# main.net
KiCad netlist of a schematic drawn in EAGLE
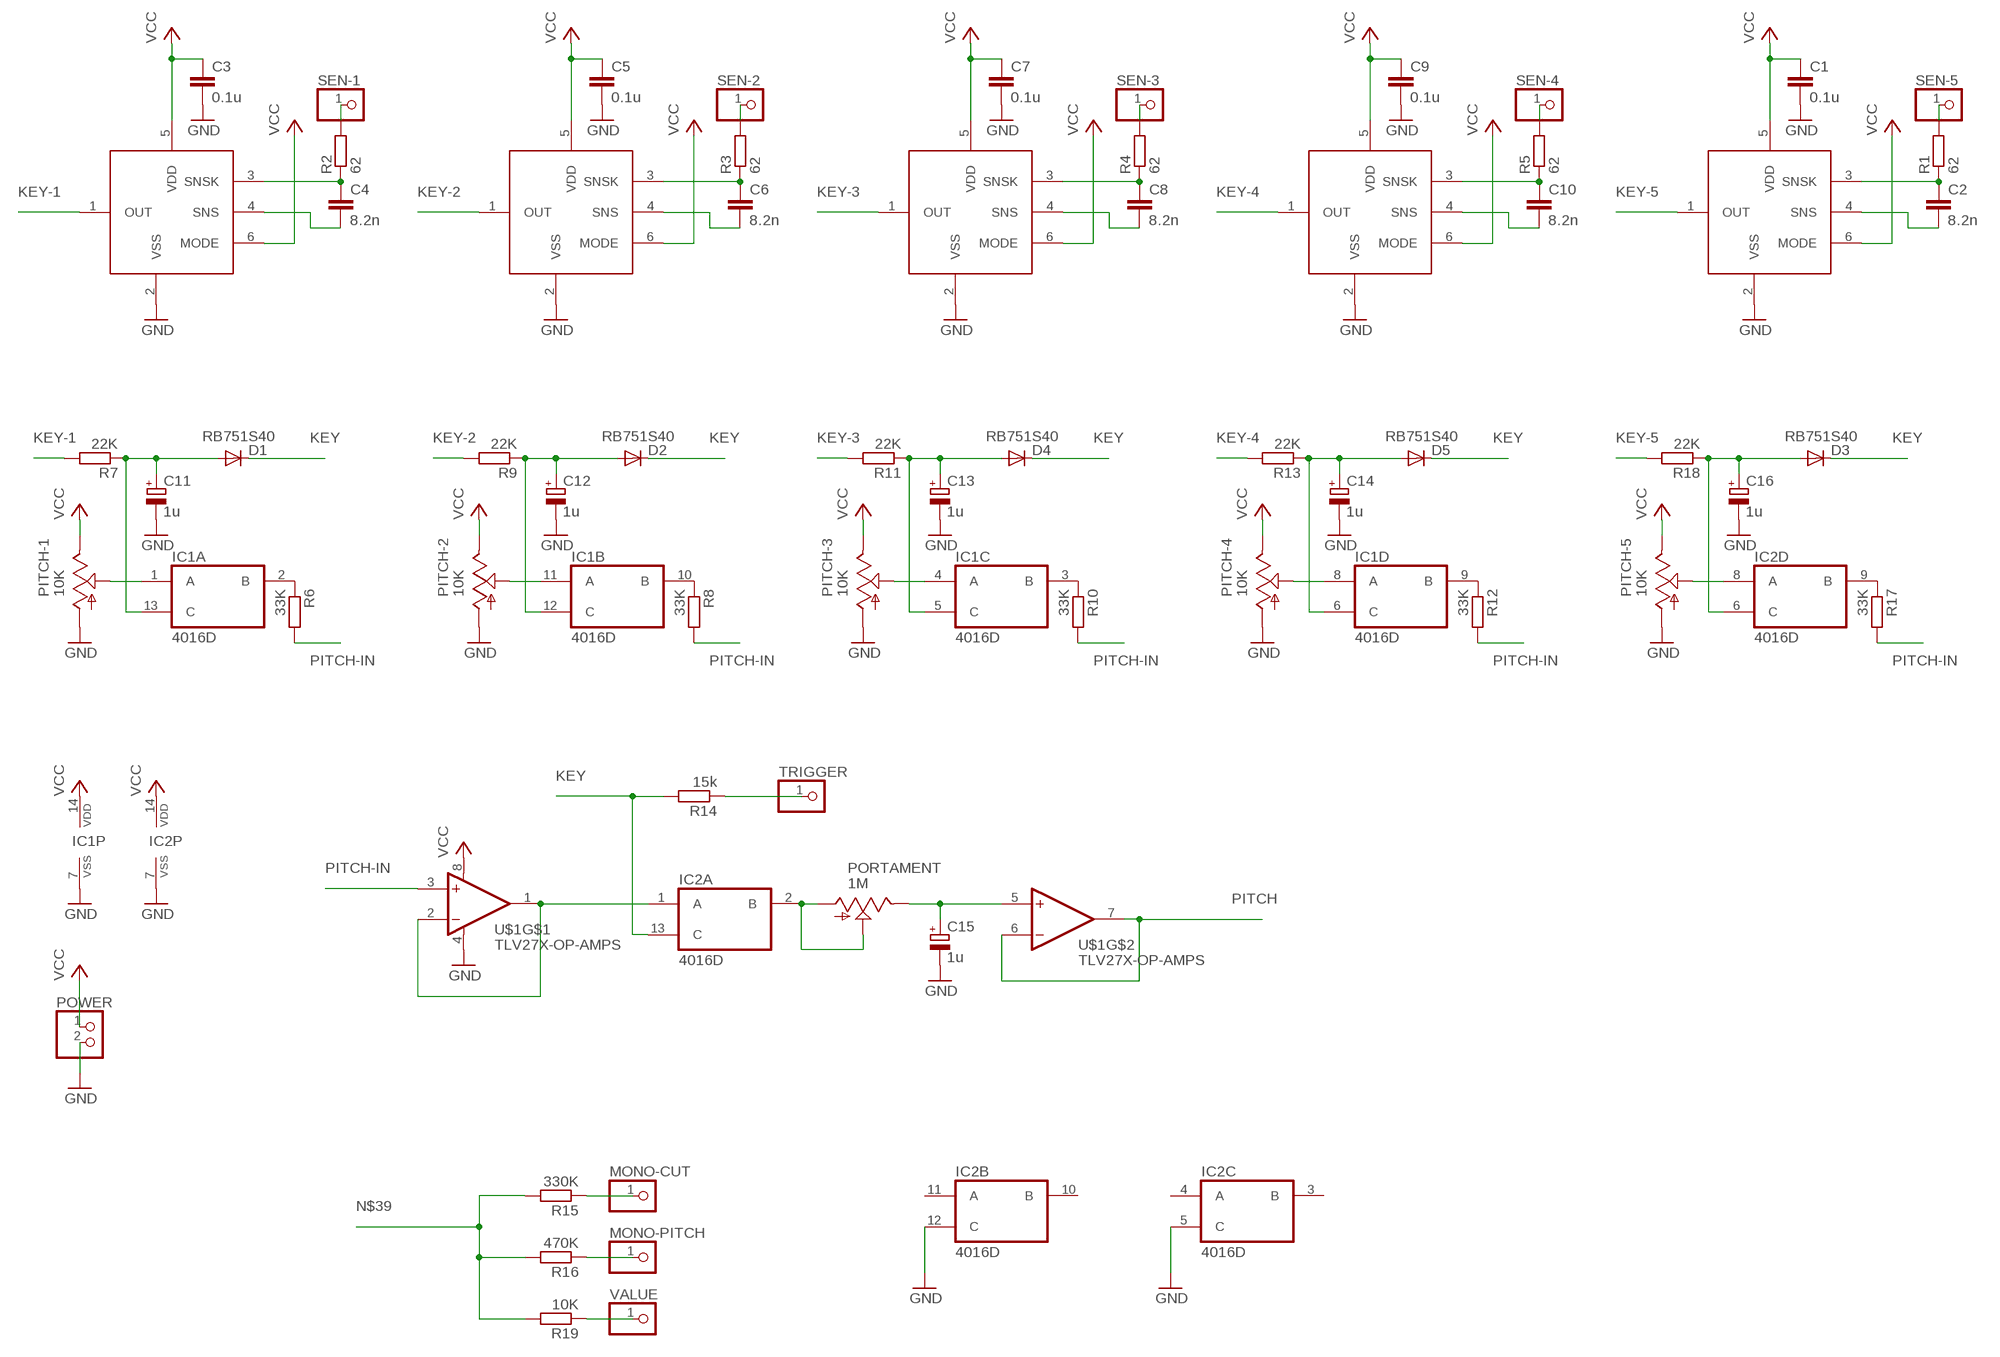
[diagram p0: schematic, sheet 1]

(export (version "E")
  (design (tool "Eeschema 10.0.6"))
  (components
    (comp (ref "C1")
      (value "0.1u")
      (footprint "eagle-import:C0805")
      (libsource (lib "eagle-import") (part "C-EUC0805"))
    )
    (comp (ref "C2")
      (value "8.2n")
      (footprint "eagle-import:C0805")
      (libsource (lib "eagle-import") (part "C-EUC0805"))
    )
    (comp (ref "C3")
      (value "0.1u")
      (footprint "eagle-import:C0805")
      (libsource (lib "eagle-import") (part "C-EUC0805"))
    )
    (comp (ref "C4")
      (value "8.2n")
      (footprint "eagle-import:C0805")
      (libsource (lib "eagle-import") (part "C-EUC0805"))
    )
    (comp (ref "C5")
      (value "0.1u")
      (footprint "eagle-import:C0805")
      (libsource (lib "eagle-import") (part "C-EUC0805"))
    )
    (comp (ref "C6")
      (value "8.2n")
      (footprint "eagle-import:C0805")
      (libsource (lib "eagle-import") (part "C-EUC0805"))
    )
    (comp (ref "C7")
      (value "0.1u")
      (footprint "eagle-import:C0805")
      (libsource (lib "eagle-import") (part "C-EUC0805"))
    )
    (comp (ref "C8")
      (value "8.2n")
      (footprint "eagle-import:C0805")
      (libsource (lib "eagle-import") (part "C-EUC0805"))
    )
    (comp (ref "C9")
      (value "0.1u")
      (footprint "eagle-import:C0805")
      (libsource (lib "eagle-import") (part "C-EUC0805"))
    )
    (comp (ref "C10")
      (value "8.2n")
      (footprint "eagle-import:C0805")
      (libsource (lib "eagle-import") (part "C-EUC0805"))
    )
    (comp (ref "C11")
      (value "1u")
      (footprint "eagle-import:PANASONIC_A")
      (libsource (lib "eagle-import") (part "CPOL-EUA"))
    )
    (comp (ref "C12")
      (value "1u")
      (footprint "eagle-import:PANASONIC_A")
      (libsource (lib "eagle-import") (part "CPOL-EUA"))
    )
    (comp (ref "C13")
      (value "1u")
      (footprint "eagle-import:PANASONIC_A")
      (libsource (lib "eagle-import") (part "CPOL-EUA"))
    )
    (comp (ref "C14")
      (value "1u")
      (footprint "eagle-import:PANASONIC_A")
      (libsource (lib "eagle-import") (part "CPOL-EUA"))
    )
    (comp (ref "C15")
      (value "1u")
      (footprint "eagle-import:PANASONIC_A")
      (libsource (lib "eagle-import") (part "CPOL-EUA"))
    )
    (comp (ref "C16")
      (value "1u")
      (footprint "eagle-import:PANASONIC_A")
      (libsource (lib "eagle-import") (part "CPOL-EUA"))
    )
    (comp (ref "D1")
      (value "RB751S40")
      (footprint "eagle-import:SOD523")
      (libsource (lib "eagle-import") (part "DIODE-SOD523"))
    )
    (comp (ref "D2")
      (value "RB751S40")
      (footprint "eagle-import:SOD523")
      (libsource (lib "eagle-import") (part "DIODE-SOD523"))
    )
    (comp (ref "D3")
      (value "RB751S40")
      (footprint "eagle-import:SOD523")
      (libsource (lib "eagle-import") (part "DIODE-SOD523"))
    )
    (comp (ref "D4")
      (value "RB751S40")
      (footprint "eagle-import:SOD523")
      (libsource (lib "eagle-import") (part "DIODE-SOD523"))
    )
    (comp (ref "D5")
      (value "RB751S40")
      (footprint "eagle-import:SOD523")
      (libsource (lib "eagle-import") (part "DIODE-SOD523"))
    )
    (comp (ref "IC1")
      (value "4016D")
      (footprint "eagle-import:SO14")
      (libsource (lib "eagle-import") (part "4016D"))
    )
    (comp (ref "IC2")
      (value "4016D")
      (footprint "eagle-import:SO14")
      (libsource (lib "eagle-import") (part "4016D"))
    )
    (comp (ref "MONO-CUT")
      (value "PINHD-1X1")
      (footprint "eagle-import:1X01")
      (libsource (lib "eagle-import") (part "PINHD-1X1"))
    )
    (comp (ref "MONO-PITCH")
      (value "PINHD-1X1")
      (footprint "eagle-import:1X01")
      (libsource (lib "eagle-import") (part "PINHD-1X1"))
    )
    (comp (ref "PITCH-1")
      (value "10K")
      (footprint "eagle-import:PIN-1X03")
      (libsource (lib "eagle-import") (part "POT-PINHEADSTRAIGHT"))
    )
    (comp (ref "PITCH-2")
      (value "10K")
      (footprint "eagle-import:PIN-1X03")
      (libsource (lib "eagle-import") (part "POT-PINHEADSTRAIGHT"))
    )
    (comp (ref "PITCH-3")
      (value "10K")
      (footprint "eagle-import:PIN-1X03")
      (libsource (lib "eagle-import") (part "POT-PINHEADSTRAIGHT"))
    )
    (comp (ref "PITCH-4")
      (value "10K")
      (footprint "eagle-import:PIN-1X03")
      (libsource (lib "eagle-import") (part "POT-PINHEADSTRAIGHT"))
    )
    (comp (ref "PITCH-5")
      (value "10K")
      (footprint "eagle-import:PIN-1X03")
      (libsource (lib "eagle-import") (part "POT-PINHEADSTRAIGHT"))
    )
    (comp (ref "PORTAMENT")
      (value "1M")
      (footprint "eagle-import:PIN-1X03")
      (libsource (lib "eagle-import") (part "POT-PINHEADSTRAIGHT"))
    )
    (comp (ref "POWER")
      (value "PINHD-1X2")
      (footprint "eagle-import:1X02")
      (libsource (lib "eagle-import") (part "PINHD-1X2"))
    )
    (comp (ref "R1")
      (value "62")
      (footprint "eagle-import:R0805")
      (libsource (lib "eagle-import") (part "R-EU_R0805"))
    )
    (comp (ref "R2")
      (value "62")
      (footprint "eagle-import:R0805")
      (libsource (lib "eagle-import") (part "R-EU_R0805"))
    )
    (comp (ref "R3")
      (value "62")
      (footprint "eagle-import:R0805")
      (libsource (lib "eagle-import") (part "R-EU_R0805"))
    )
    (comp (ref "R4")
      (value "62")
      (footprint "eagle-import:R0805")
      (libsource (lib "eagle-import") (part "R-EU_R0805"))
    )
    (comp (ref "R5")
      (value "62")
      (footprint "eagle-import:R0805")
      (libsource (lib "eagle-import") (part "R-EU_R0805"))
    )
    (comp (ref "R6")
      (value "33K")
      (footprint "eagle-import:R0805")
      (libsource (lib "eagle-import") (part "R-EU_R0805"))
    )
    (comp (ref "R7")
      (value "22K")
      (footprint "eagle-import:R0805")
      (libsource (lib "eagle-import") (part "R-EU_R0805"))
    )
    (comp (ref "R8")
      (value "33K")
      (footprint "eagle-import:R0805")
      (libsource (lib "eagle-import") (part "R-EU_R0805"))
    )
    (comp (ref "R9")
      (value "22K")
      (footprint "eagle-import:R0805")
      (libsource (lib "eagle-import") (part "R-EU_R0805"))
    )
    (comp (ref "R10")
      (value "33K")
      (footprint "eagle-import:R0805")
      (libsource (lib "eagle-import") (part "R-EU_R0805"))
    )
    (comp (ref "R11")
      (value "22K")
      (footprint "eagle-import:R0805")
      (libsource (lib "eagle-import") (part "R-EU_R0805"))
    )
    (comp (ref "R12")
      (value "33K")
      (footprint "eagle-import:R0805")
      (libsource (lib "eagle-import") (part "R-EU_R0805"))
    )
    (comp (ref "R13")
      (value "22K")
      (footprint "eagle-import:R0805")
      (libsource (lib "eagle-import") (part "R-EU_R0805"))
    )
    (comp (ref "R14")
      (value "15k")
      (footprint "eagle-import:R0805")
      (libsource (lib "eagle-import") (part "R-EU_R0805"))
    )
    (comp (ref "R15")
      (value "330K")
      (footprint "eagle-import:R0805")
      (libsource (lib "eagle-import") (part "R-EU_R0805"))
    )
    (comp (ref "R16")
      (value "470K")
      (footprint "eagle-import:R0805")
      (libsource (lib "eagle-import") (part "R-EU_R0805"))
    )
    (comp (ref "R17")
      (value "33K")
      (footprint "eagle-import:R0805")
      (libsource (lib "eagle-import") (part "R-EU_R0805"))
    )
    (comp (ref "R18")
      (value "22K")
      (footprint "eagle-import:R0805")
      (libsource (lib "eagle-import") (part "R-EU_R0805"))
    )
    (comp (ref "R19")
      (value "10K")
      (footprint "eagle-import:R0805")
      (libsource (lib "eagle-import") (part "R-EU_R0805"))
    )
    (comp (ref "SEN-1")
      (value "PINHD-1X1")
      (footprint "eagle-import:1X01")
      (libsource (lib "eagle-import") (part "PINHD-1X1"))
    )
    (comp (ref "SEN-2")
      (value "PINHD-1X1")
      (footprint "eagle-import:1X01")
      (libsource (lib "eagle-import") (part "PINHD-1X1"))
    )
    (comp (ref "SEN-3")
      (value "PINHD-1X1")
      (footprint "eagle-import:1X01")
      (libsource (lib "eagle-import") (part "PINHD-1X1"))
    )
    (comp (ref "SEN-4")
      (value "PINHD-1X1")
      (footprint "eagle-import:1X01")
      (libsource (lib "eagle-import") (part "PINHD-1X1"))
    )
    (comp (ref "SEN-5")
      (value "PINHD-1X1")
      (footprint "eagle-import:1X01")
      (libsource (lib "eagle-import") (part "PINHD-1X1"))
    )
    (comp (ref "TRIGGER")
      (value "PINHD-1X1")
      (footprint "eagle-import:1X01")
      (libsource (lib "eagle-import") (part "PINHD-1X1"))
    )
    (comp (ref "U$1")
      (value "TLV27X-OP-AMPS")
      (footprint "eagle-import:SOIC8")
      (libsource (lib "eagle-import") (part "TLV27X-OP-AMPS"))
    )
    (comp (ref "U$2")
      (value "AT42QT1010")
      (footprint "eagle-import:SOT23-6L")
      (libsource (lib "eagle-import") (part "AT42QT1010"))
    )
    (comp (ref "U$3")
      (value "AT42QT1010")
      (footprint "eagle-import:SOT23-6L")
      (libsource (lib "eagle-import") (part "AT42QT1010"))
    )
    (comp (ref "U$4")
      (value "AT42QT1010")
      (footprint "eagle-import:SOT23-6L")
      (libsource (lib "eagle-import") (part "AT42QT1010"))
    )
    (comp (ref "U$5")
      (value "AT42QT1010")
      (footprint "eagle-import:SOT23-6L")
      (libsource (lib "eagle-import") (part "AT42QT1010"))
    )
    (comp (ref "U$6")
      (value "AT42QT1010")
      (footprint "eagle-import:SOT23-6L")
      (libsource (lib "eagle-import") (part "AT42QT1010"))
    )
    (comp (ref "VALUE")
      (value "PINHD-1X1")
      (footprint "eagle-import:1X01")
      (libsource (lib "eagle-import") (part "PINHD-1X1"))
    )
  )
  (nets
    (net (code "1") (name "/KEY") (class "Default")
      (node (ref "D1") (pin "C") (pinfunction "C_C") (pintype "passive"))
      (node (ref "D2") (pin "C") (pinfunction "C_C") (pintype "passive"))
      (node (ref "D3") (pin "C") (pinfunction "C_C") (pintype "passive"))
      (node (ref "D4") (pin "C") (pinfunction "C_C") (pintype "passive"))
      (node (ref "D5") (pin "C") (pinfunction "C_C") (pintype "passive"))
      (node (ref "IC2") (pin "13") (pinfunction "C_13") (pintype "input"))
      (node (ref "R14") (pin "2") (pinfunction "2_2") (pintype "passive"))
    )
    (net (code "2") (name "/KEY-1") (class "Default")
      (node (ref "R7") (pin "2") (pinfunction "2_2") (pintype "passive"))
      (node (ref "U$2") (pin "1") (pinfunction "OUT_1") (pintype "output"))
    )
    (net (code "3") (name "/KEY-2") (class "Default")
      (node (ref "R9") (pin "2") (pinfunction "2_2") (pintype "passive"))
      (node (ref "U$3") (pin "1") (pinfunction "OUT_1") (pintype "output"))
    )
    (net (code "4") (name "/KEY-3") (class "Default")
      (node (ref "R11") (pin "2") (pinfunction "2_2") (pintype "passive"))
      (node (ref "U$4") (pin "1") (pinfunction "OUT_1") (pintype "output"))
    )
    (net (code "5") (name "/KEY-4") (class "Default")
      (node (ref "R13") (pin "2") (pinfunction "2_2") (pintype "passive"))
      (node (ref "U$5") (pin "1") (pinfunction "OUT_1") (pintype "output"))
    )
    (net (code "6") (name "/KEY-5") (class "Default")
      (node (ref "R18") (pin "2") (pinfunction "2_2") (pintype "passive"))
      (node (ref "U$6") (pin "1") (pinfunction "OUT_1") (pintype "output"))
    )
    (net (code "7") (name "/N$39") (class "Default")
      (node (ref "R15") (pin "2") (pinfunction "2_2") (pintype "passive"))
      (node (ref "R16") (pin "2") (pinfunction "2_2") (pintype "passive"))
      (node (ref "R19") (pin "2") (pinfunction "2_2") (pintype "passive"))
    )
    (net (code "8") (name "/PITCH") (class "Default")
      (node (ref "U$1") (pin "6") (pinfunction "-IN_6") (pintype "input"))
      (node (ref "U$1") (pin "7") (pinfunction "OUT_7") (pintype "output"))
    )
    (net (code "9") (name "/PITCH-IN") (class "Default")
      (node (ref "R10") (pin "2") (pinfunction "2_2") (pintype "passive"))
      (node (ref "R12") (pin "2") (pinfunction "2_2") (pintype "passive"))
      (node (ref "R17") (pin "2") (pinfunction "2_2") (pintype "passive"))
      (node (ref "R6") (pin "2") (pinfunction "2_2") (pintype "passive"))
      (node (ref "R8") (pin "2") (pinfunction "2_2") (pintype "passive"))
      (node (ref "U$1") (pin "3") (pinfunction "+IN_3") (pintype "input"))
    )
    (net (code "10") (name "GND") (class "Default")
      (node (ref "C1") (pin "2") (pinfunction "2_2") (pintype "passive"))
      (node (ref "C11") (pin "-") (pinfunction "-_-") (pintype "passive"))
      (node (ref "C12") (pin "-") (pinfunction "-_-") (pintype "passive"))
      (node (ref "C13") (pin "-") (pinfunction "-_-") (pintype "passive"))
      (node (ref "C14") (pin "-") (pinfunction "-_-") (pintype "passive"))
      (node (ref "C15") (pin "-") (pinfunction "-_-") (pintype "passive"))
      (node (ref "C16") (pin "-") (pinfunction "-_-") (pintype "passive"))
      (node (ref "C3") (pin "2") (pinfunction "2_2") (pintype "passive"))
      (node (ref "C5") (pin "2") (pinfunction "2_2") (pintype "passive"))
      (node (ref "C7") (pin "2") (pinfunction "2_2") (pintype "passive"))
      (node (ref "C9") (pin "2") (pinfunction "2_2") (pintype "passive"))
      (node (ref "IC1") (pin "7") (pinfunction "VSS_7") (pintype "power_in"))
      (node (ref "IC2") (pin "12") (pinfunction "C_12") (pintype "input"))
      (node (ref "IC2") (pin "5") (pinfunction "C_5") (pintype "input"))
      (node (ref "IC2") (pin "7") (pinfunction "VSS_7") (pintype "power_in"))
      (node (ref "PITCH-1") (pin "1") (pinfunction "A_1") (pintype "passive"))
      (node (ref "PITCH-2") (pin "1") (pinfunction "A_1") (pintype "passive"))
      (node (ref "PITCH-3") (pin "1") (pinfunction "A_1") (pintype "passive"))
      (node (ref "PITCH-4") (pin "1") (pinfunction "A_1") (pintype "passive"))
      (node (ref "PITCH-5") (pin "1") (pinfunction "A_1") (pintype "passive"))
      (node (ref "POWER") (pin "2") (pinfunction "2_2") (pintype "passive"))
      (node (ref "U$1") (pin "4") (pinfunction "V-_4") (pintype "power_in"))
      (node (ref "U$2") (pin "2") (pinfunction "VSS_2") (pintype "power_in"))
      (node (ref "U$3") (pin "2") (pinfunction "VSS_2") (pintype "power_in"))
      (node (ref "U$4") (pin "2") (pinfunction "VSS_2") (pintype "power_in"))
      (node (ref "U$5") (pin "2") (pinfunction "VSS_2") (pintype "power_in"))
      (node (ref "U$6") (pin "2") (pinfunction "VSS_2") (pintype "power_in"))
    )
    (net (code "11") (name "Net-(IC1A-A)") (class "Default")
      (node (ref "IC1") (pin "1") (pinfunction "A_1") (pintype "tri_state"))
      (node (ref "PITCH-1") (pin "2") (pinfunction "S_2") (pintype "passive"))
    )
    (net (code "12") (name "Net-(IC1A-B)") (class "Default")
      (node (ref "IC1") (pin "2") (pinfunction "B_2") (pintype "tri_state"))
      (node (ref "R6") (pin "1") (pinfunction "1_1") (pintype "passive"))
    )
    (net (code "13") (name "Net-(IC1A-C)") (class "Default")
      (node (ref "C11") (pin "+") (pinfunction "+_+") (pintype "passive"))
      (node (ref "D1") (pin "A") (pinfunction "A_A") (pintype "passive"))
      (node (ref "IC1") (pin "13") (pinfunction "C_13") (pintype "input"))
      (node (ref "R7") (pin "1") (pinfunction "1_1") (pintype "passive"))
    )
    (net (code "14") (name "Net-(IC1B-A)") (class "Default")
      (node (ref "IC1") (pin "11") (pinfunction "A_11") (pintype "tri_state"))
      (node (ref "PITCH-2") (pin "2") (pinfunction "S_2") (pintype "passive"))
    )
    (net (code "15") (name "Net-(IC1B-B)") (class "Default")
      (node (ref "IC1") (pin "10") (pinfunction "B_10") (pintype "tri_state"))
      (node (ref "R8") (pin "1") (pinfunction "1_1") (pintype "passive"))
    )
    (net (code "16") (name "Net-(IC1B-C)") (class "Default")
      (node (ref "C12") (pin "+") (pinfunction "+_+") (pintype "passive"))
      (node (ref "D2") (pin "A") (pinfunction "A_A") (pintype "passive"))
      (node (ref "IC1") (pin "12") (pinfunction "C_12") (pintype "input"))
      (node (ref "R9") (pin "1") (pinfunction "1_1") (pintype "passive"))
    )
    (net (code "17") (name "Net-(IC1C-A)") (class "Default")
      (node (ref "IC1") (pin "4") (pinfunction "A_4") (pintype "tri_state"))
      (node (ref "PITCH-3") (pin "2") (pinfunction "S_2") (pintype "passive"))
    )
    (net (code "18") (name "Net-(IC1C-B)") (class "Default")
      (node (ref "IC1") (pin "3") (pinfunction "B_3") (pintype "tri_state"))
      (node (ref "R10") (pin "1") (pinfunction "1_1") (pintype "passive"))
    )
    (net (code "19") (name "Net-(IC1C-C)") (class "Default")
      (node (ref "C13") (pin "+") (pinfunction "+_+") (pintype "passive"))
      (node (ref "D4") (pin "A") (pinfunction "A_A") (pintype "passive"))
      (node (ref "IC1") (pin "5") (pinfunction "C_5") (pintype "input"))
      (node (ref "R11") (pin "1") (pinfunction "1_1") (pintype "passive"))
    )
    (net (code "20") (name "Net-(IC1D-A)") (class "Default")
      (node (ref "IC1") (pin "8") (pinfunction "A_8") (pintype "tri_state"))
      (node (ref "PITCH-4") (pin "2") (pinfunction "S_2") (pintype "passive"))
    )
    (net (code "21") (name "Net-(IC1D-B)") (class "Default")
      (node (ref "IC1") (pin "9") (pinfunction "B_9") (pintype "tri_state"))
      (node (ref "R12") (pin "1") (pinfunction "1_1") (pintype "passive"))
    )
    (net (code "22") (name "Net-(IC1D-C)") (class "Default")
      (node (ref "C14") (pin "+") (pinfunction "+_+") (pintype "passive"))
      (node (ref "D5") (pin "A") (pinfunction "A_A") (pintype "passive"))
      (node (ref "IC1") (pin "6") (pinfunction "C_6") (pintype "input"))
      (node (ref "R13") (pin "1") (pinfunction "1_1") (pintype "passive"))
    )
    (net (code "23") (name "Net-(IC2A-A)") (class "Default")
      (node (ref "IC2") (pin "1") (pinfunction "A_1") (pintype "tri_state"))
      (node (ref "U$1") (pin "1") (pinfunction "OUT_1") (pintype "output"))
      (node (ref "U$1") (pin "2") (pinfunction "-IN_2") (pintype "input"))
    )
    (net (code "24") (name "Net-(IC2A-B)") (class "Default")
      (node (ref "IC2") (pin "2") (pinfunction "B_2") (pintype "tri_state"))
      (node (ref "PORTAMENT") (pin "1") (pinfunction "A_1") (pintype "passive"))
      (node (ref "PORTAMENT") (pin "2") (pinfunction "S_2") (pintype "passive"))
    )
    (net (code "25") (name "Net-(IC2D-A)") (class "Default")
      (node (ref "IC2") (pin "8") (pinfunction "A_8") (pintype "tri_state"))
      (node (ref "PITCH-5") (pin "2") (pinfunction "S_2") (pintype "passive"))
    )
    (net (code "26") (name "Net-(IC2D-B)") (class "Default")
      (node (ref "IC2") (pin "9") (pinfunction "B_9") (pintype "tri_state"))
      (node (ref "R17") (pin "1") (pinfunction "1_1") (pintype "passive"))
    )
    (net (code "27") (name "Net-(IC2D-C)") (class "Default")
      (node (ref "C16") (pin "+") (pinfunction "+_+") (pintype "passive"))
      (node (ref "D3") (pin "A") (pinfunction "A_A") (pintype "passive"))
      (node (ref "IC2") (pin "6") (pinfunction "C_6") (pintype "input"))
      (node (ref "R18") (pin "1") (pinfunction "1_1") (pintype "passive"))
    )
    (net (code "28") (name "Net-(MONO-CUT-Pad1)") (class "Default")
      (node (ref "MONO-CUT") (pin "1") (pinfunction "1_1") (pintype "passive"))
      (node (ref "R15") (pin "1") (pinfunction "1_1") (pintype "passive"))
    )
    (net (code "29") (name "Net-(MONO-PITCH-Pad1)") (class "Default")
      (node (ref "MONO-PITCH") (pin "1") (pinfunction "1_1") (pintype "passive"))
      (node (ref "R16") (pin "1") (pinfunction "1_1") (pintype "passive"))
    )
    (net (code "30") (name "Net-(PORTAMENT-E)") (class "Default")
      (node (ref "C15") (pin "+") (pinfunction "+_+") (pintype "passive"))
      (node (ref "PORTAMENT") (pin "3") (pinfunction "E_3") (pintype "passive"))
      (node (ref "U$1") (pin "5") (pinfunction "+IN_5") (pintype "input"))
    )
    (net (code "31") (name "Net-(R1-Pad2)") (class "Default")
      (node (ref "R1") (pin "2") (pinfunction "2_2") (pintype "passive"))
      (node (ref "SEN-5") (pin "1") (pinfunction "1_1") (pintype "passive"))
    )
    (net (code "32") (name "Net-(R2-Pad2)") (class "Default")
      (node (ref "R2") (pin "2") (pinfunction "2_2") (pintype "passive"))
      (node (ref "SEN-1") (pin "1") (pinfunction "1_1") (pintype "passive"))
    )
    (net (code "33") (name "Net-(R3-Pad2)") (class "Default")
      (node (ref "R3") (pin "2") (pinfunction "2_2") (pintype "passive"))
      (node (ref "SEN-2") (pin "1") (pinfunction "1_1") (pintype "passive"))
    )
    (net (code "34") (name "Net-(R4-Pad2)") (class "Default")
      (node (ref "R4") (pin "2") (pinfunction "2_2") (pintype "passive"))
      (node (ref "SEN-3") (pin "1") (pinfunction "1_1") (pintype "passive"))
    )
    (net (code "35") (name "Net-(R5-Pad2)") (class "Default")
      (node (ref "R5") (pin "2") (pinfunction "2_2") (pintype "passive"))
      (node (ref "SEN-4") (pin "1") (pinfunction "1_1") (pintype "passive"))
    )
    (net (code "36") (name "Net-(R14-Pad1)") (class "Default")
      (node (ref "R14") (pin "1") (pinfunction "1_1") (pintype "passive"))
      (node (ref "TRIGGER") (pin "1") (pinfunction "1_1") (pintype "passive"))
    )
    (net (code "37") (name "Net-(R19-Pad1)") (class "Default")
      (node (ref "R19") (pin "1") (pinfunction "1_1") (pintype "passive"))
      (node (ref "VALUE") (pin "1") (pinfunction "1_1") (pintype "passive"))
    )
    (net (code "38") (name "Net-(U$2-SNS)") (class "Default")
      (node (ref "C4") (pin "2") (pinfunction "2_2") (pintype "passive"))
      (node (ref "U$2") (pin "4") (pinfunction "SNS_4") (pintype "bidirectional"))
    )
    (net (code "39") (name "Net-(U$2-SNSK)") (class "Default")
      (node (ref "C4") (pin "1") (pinfunction "1_1") (pintype "passive"))
      (node (ref "R2") (pin "1") (pinfunction "1_1") (pintype "passive"))
      (node (ref "U$2") (pin "3") (pinfunction "SNSK_3") (pintype "bidirectional"))
    )
    (net (code "40") (name "Net-(U$3-SNS)") (class "Default")
      (node (ref "C6") (pin "2") (pinfunction "2_2") (pintype "passive"))
      (node (ref "U$3") (pin "4") (pinfunction "SNS_4") (pintype "bidirectional"))
    )
    (net (code "41") (name "Net-(U$3-SNSK)") (class "Default")
      (node (ref "C6") (pin "1") (pinfunction "1_1") (pintype "passive"))
      (node (ref "R3") (pin "1") (pinfunction "1_1") (pintype "passive"))
      (node (ref "U$3") (pin "3") (pinfunction "SNSK_3") (pintype "bidirectional"))
    )
    (net (code "42") (name "Net-(U$4-SNS)") (class "Default")
      (node (ref "C8") (pin "2") (pinfunction "2_2") (pintype "passive"))
      (node (ref "U$4") (pin "4") (pinfunction "SNS_4") (pintype "bidirectional"))
    )
    (net (code "43") (name "Net-(U$4-SNSK)") (class "Default")
      (node (ref "C8") (pin "1") (pinfunction "1_1") (pintype "passive"))
      (node (ref "R4") (pin "1") (pinfunction "1_1") (pintype "passive"))
      (node (ref "U$4") (pin "3") (pinfunction "SNSK_3") (pintype "bidirectional"))
    )
    (net (code "44") (name "Net-(U$5-SNS)") (class "Default")
      (node (ref "C10") (pin "2") (pinfunction "2_2") (pintype "passive"))
      (node (ref "U$5") (pin "4") (pinfunction "SNS_4") (pintype "bidirectional"))
    )
    (net (code "45") (name "Net-(U$5-SNSK)") (class "Default")
      (node (ref "C10") (pin "1") (pinfunction "1_1") (pintype "passive"))
      (node (ref "R5") (pin "1") (pinfunction "1_1") (pintype "passive"))
      (node (ref "U$5") (pin "3") (pinfunction "SNSK_3") (pintype "bidirectional"))
    )
    (net (code "46") (name "Net-(U$6-SNS)") (class "Default")
      (node (ref "C2") (pin "2") (pinfunction "2_2") (pintype "passive"))
      (node (ref "U$6") (pin "4") (pinfunction "SNS_4") (pintype "bidirectional"))
    )
    (net (code "47") (name "Net-(U$6-SNSK)") (class "Default")
      (node (ref "C2") (pin "1") (pinfunction "1_1") (pintype "passive"))
      (node (ref "R1") (pin "1") (pinfunction "1_1") (pintype "passive"))
      (node (ref "U$6") (pin "3") (pinfunction "SNSK_3") (pintype "bidirectional"))
    )
    (net (code "48") (name "VCC") (class "Default")
      (node (ref "C1") (pin "1") (pinfunction "1_1") (pintype "passive"))
      (node (ref "C3") (pin "1") (pinfunction "1_1") (pintype "passive"))
      (node (ref "C5") (pin "1") (pinfunction "1_1") (pintype "passive"))
      (node (ref "C7") (pin "1") (pinfunction "1_1") (pintype "passive"))
      (node (ref "C9") (pin "1") (pinfunction "1_1") (pintype "passive"))
      (node (ref "IC1") (pin "14") (pinfunction "VDD_14") (pintype "power_in"))
      (node (ref "IC2") (pin "14") (pinfunction "VDD_14") (pintype "power_in"))
      (node (ref "PITCH-1") (pin "3") (pinfunction "E_3") (pintype "passive"))
      (node (ref "PITCH-2") (pin "3") (pinfunction "E_3") (pintype "passive"))
      (node (ref "PITCH-3") (pin "3") (pinfunction "E_3") (pintype "passive"))
      (node (ref "PITCH-4") (pin "3") (pinfunction "E_3") (pintype "passive"))
      (node (ref "PITCH-5") (pin "3") (pinfunction "E_3") (pintype "passive"))
      (node (ref "POWER") (pin "1") (pinfunction "1_1") (pintype "passive"))
      (node (ref "U$1") (pin "8") (pinfunction "V+_8") (pintype "power_in"))
      (node (ref "U$2") (pin "5") (pinfunction "VDD_5") (pintype "power_in"))
      (node (ref "U$2") (pin "6") (pinfunction "MODE_6") (pintype "input"))
      (node (ref "U$3") (pin "5") (pinfunction "VDD_5") (pintype "power_in"))
      (node (ref "U$3") (pin "6") (pinfunction "MODE_6") (pintype "input"))
      (node (ref "U$4") (pin "5") (pinfunction "VDD_5") (pintype "power_in"))
      (node (ref "U$4") (pin "6") (pinfunction "MODE_6") (pintype "input"))
      (node (ref "U$5") (pin "5") (pinfunction "VDD_5") (pintype "power_in"))
      (node (ref "U$5") (pin "6") (pinfunction "MODE_6") (pintype "input"))
      (node (ref "U$6") (pin "5") (pinfunction "VDD_5") (pintype "power_in"))
      (node (ref "U$6") (pin "6") (pinfunction "MODE_6") (pintype "input"))
    )
    (net (code "49") (name "unconnected-(IC2B-A-Pad11)") (class "Default")
      (node (ref "IC2") (pin "11") (pinfunction "A_11") (pintype "tri_state"))
    )
    (net (code "50") (name "unconnected-(IC2B-B-Pad10)") (class "Default")
      (node (ref "IC2") (pin "10") (pinfunction "B_10") (pintype "tri_state"))
    )
    (net (code "51") (name "unconnected-(IC2C-A-Pad4)") (class "Default")
      (node (ref "IC2") (pin "4") (pinfunction "A_4") (pintype "tri_state"))
    )
    (net (code "52") (name "unconnected-(IC2C-B-Pad3)") (class "Default")
      (node (ref "IC2") (pin "3") (pinfunction "B_3") (pintype "tri_state"))
    )
  )
)
